# ai_candle.net
KiCad netlist of a schematic drawn in EAGLE
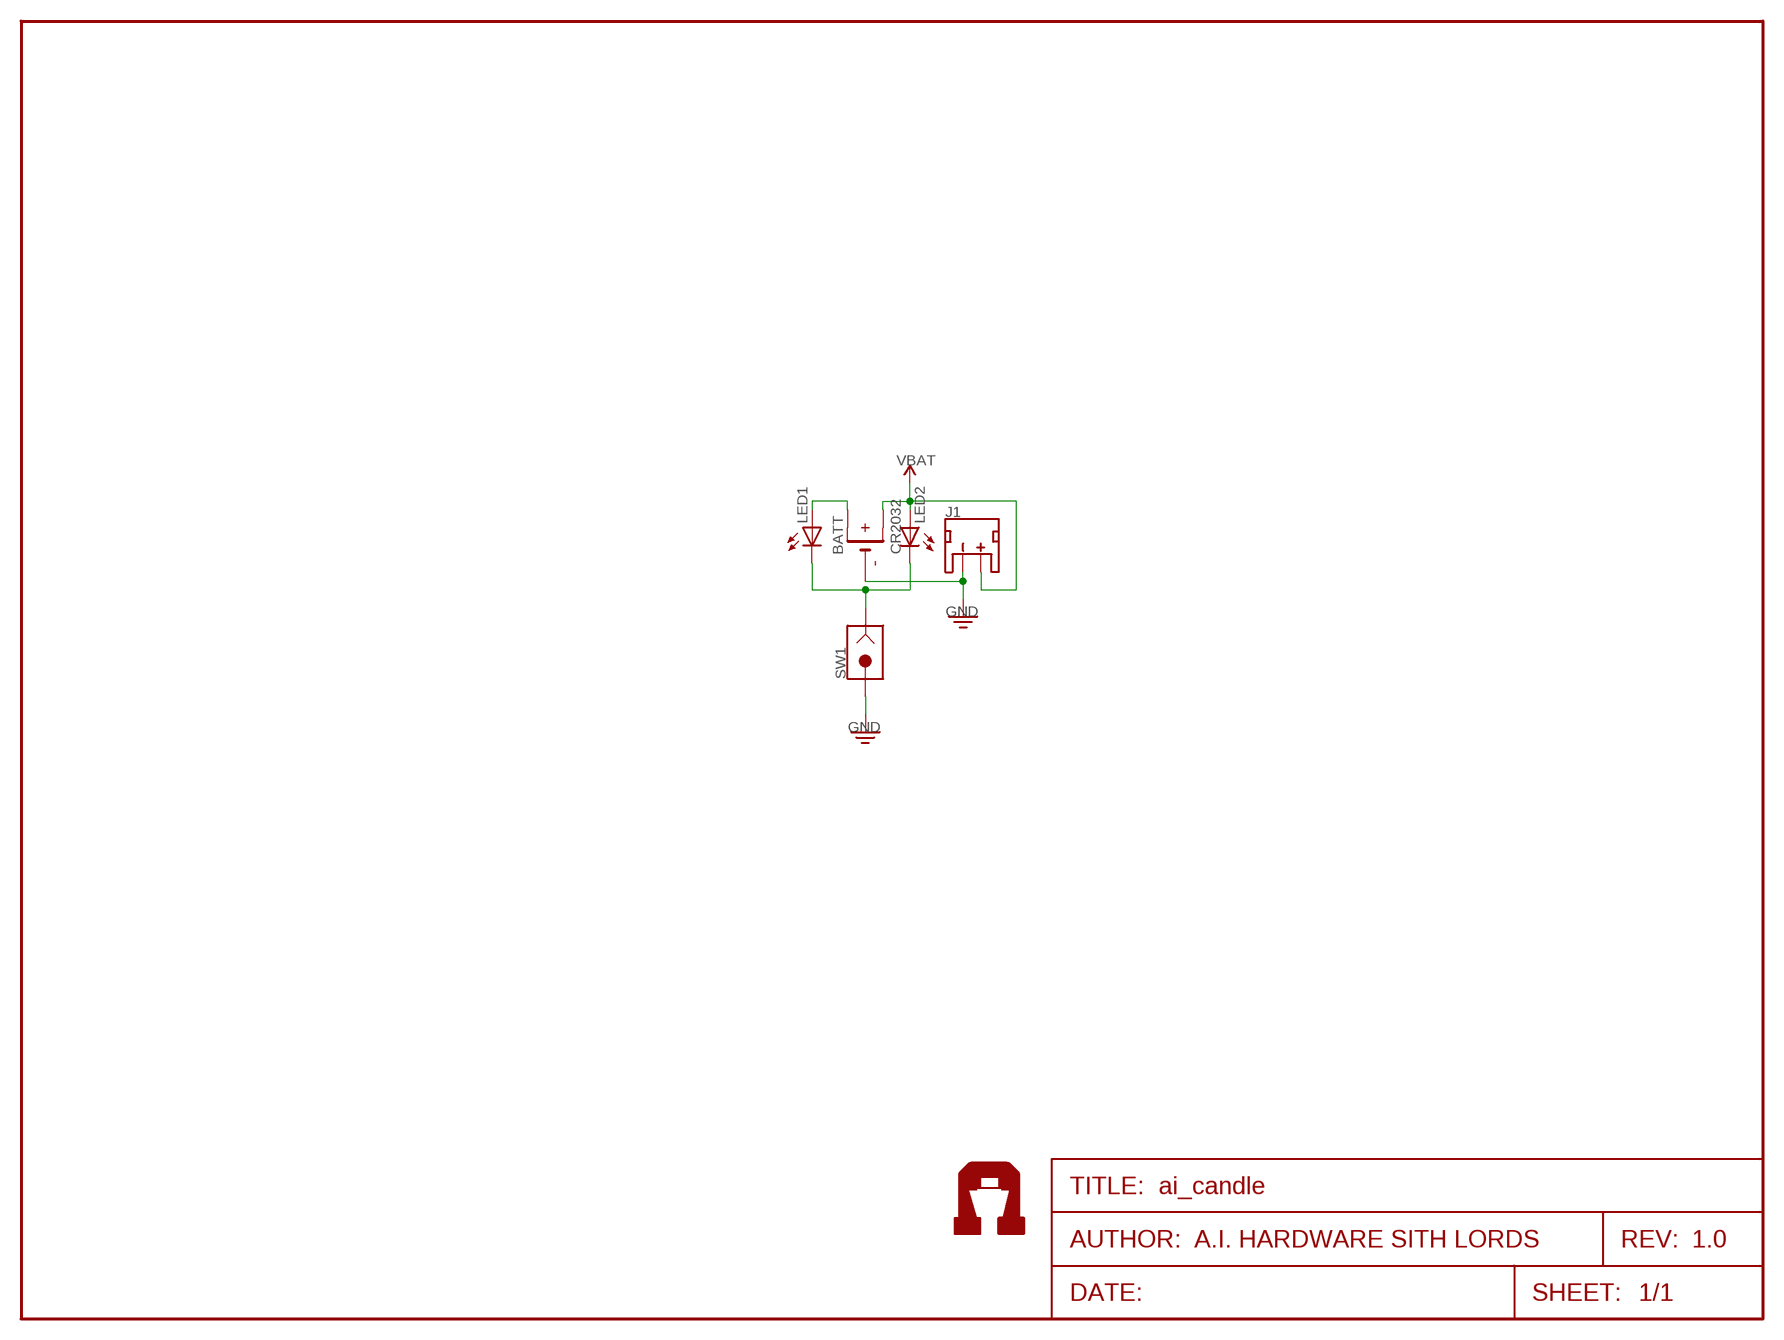
[diagram p0: schematic, sheet 1]

(export (version "E")
  (design (tool "Eeschema 10.0.6"))
  (components
    (comp (ref "BATT")
      (value "CR2032")
      (footprint "eagle-import:CR2032-TH")
      (libsource (lib "eagle-import") (part "CR2032"))
    )
    (comp (ref "J1")
      (value "JST-2-MALE")
      (footprint "eagle-import:JST-2P-SMD")
      (libsource (lib "eagle-import") (part "JST-2-MALE"))
    )
    (comp (ref "LED1")
      (value "LED5MM")
      (footprint "eagle-import:LED-5MM")
      (libsource (lib "eagle-import") (part "LED5MM"))
    )
    (comp (ref "LED2")
      (value "LED5MM")
      (footprint "eagle-import:LED-5MM")
      (libsource (lib "eagle-import") (part "LED5MM"))
    )
    (comp (ref "SW1")
      (value "TILT-SW-200D")
      (footprint "eagle-import:TILT")
      (libsource (lib "eagle-import") (part "TILT-SW-200D"))
    )
    (comp (ref "U$2")
      (value "AI-LOGOM")
      (footprint "eagle-import:AI-LOGO-M")
      (libsource (lib "eagle-import") (part "AI-LOGOM"))
    )
  )
  (nets
    (net (code "1") (name "GND") (class "Default")
      (node (ref "BATT") (pin "3") (pinfunction "-_3") (pintype "passive"))
      (node (ref "J1") (pin "2") (pinfunction "-_2") (pintype "power_in"))
      (node (ref "SW1") (pin "2") (pinfunction "1_2") (pintype "bidirectional"))
    )
    (net (code "2") (name "Net-(BATT-+-Pad1)") (class "Default")
      (node (ref "BATT") (pin "1") (pinfunction "+_1") (pintype "passive"))
      (node (ref "LED1") (pin "A") (pinfunction "A_A") (pintype "passive"))
    )
    (net (code "3") (name "Net-(SW1-2)") (class "Default")
      (node (ref "LED1") (pin "C") (pinfunction "C_C") (pintype "passive"))
      (node (ref "LED2") (pin "C") (pinfunction "C_C") (pintype "passive"))
      (node (ref "SW1") (pin "1") (pinfunction "2_1") (pintype "bidirectional"))
    )
    (net (code "4") (name "VBAT") (class "Default")
      (node (ref "BATT") (pin "2") (pinfunction "+_2") (pintype "passive"))
      (node (ref "J1") (pin "1") (pinfunction "+_1") (pintype "power_in"))
      (node (ref "LED2") (pin "A") (pinfunction "A_A") (pintype "passive"))
    )
  )
)
